# Hi_Current.net
KiCad netlist of a schematic drawn in Altium Designer
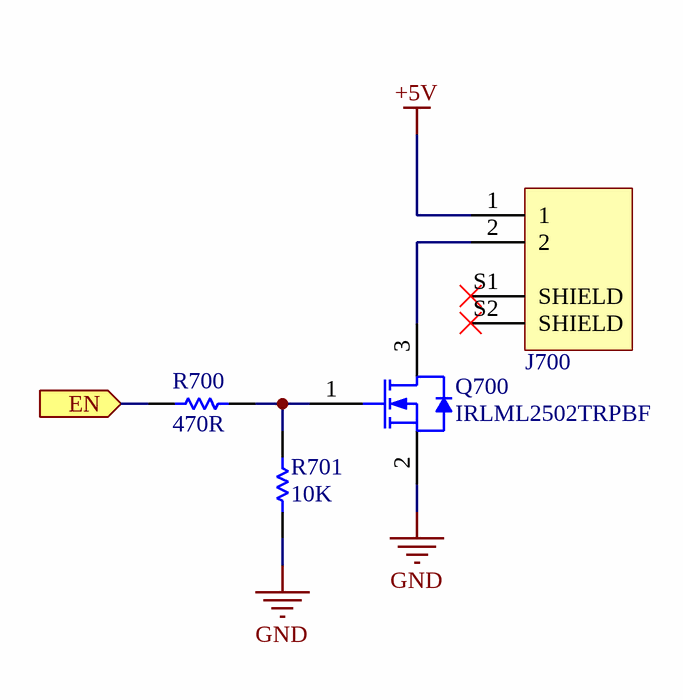
[diagram p0: Hi_Current.SchDoc]

(export (version "E")
  (design (tool "Eeschema 10.0.6"))
  (components
    (comp (ref "J700")
      (value "2 pin vertical JST GH")
      (footprint "JST_BM02B-GHS-TBT(LF)(SN)(N)")
      (description "JST GH vertical 2 pin\r\nDigiKey part no. 455-1578-1-ND")
      (fields (field (name "MF") "JST Sales") (field (name "DIGI-KEY_PART_NUMBER") "455-1580-1-ND"))
      (libsource (lib "Moonlight_Components") (part "BM02B-GHS-TBT(LF)(SN)(N)"))
    )
    (comp (ref "Q700")
      (value "IRLML2502TRPBF")
      (footprint "INTR-SOT-23-3_V")
      (description "N-Channel HEXFET(R) Power MOSFET, 20 V VDS, +/- 12 V VGS, 4.2 A, 3-Pin SOT23, RoHS, Tape and Reel")
      (fields (field (name "MANUFACTURER") "International Rectifier"))
      (libsource (lib "Moonlight_Components") (part "IRLML2502TRPBF"))
    )
    (comp (ref "R700")
      (value "470R")
      (footprint "0603_RES")
      (libsource (lib "Moonlight-Components") (part "Resistor"))
    )
    (comp (ref "R701")
      (value "10K")
      (footprint "0603_RES")
      (libsource (lib "Moonlight-Components") (part "Resistor"))
    )
  )
  (nets
    (net (code "1") (name "+5V") (class "Default")
      (node (ref "J700") (pin "1") (pinfunction "1_1") (pintype "passive"))
    )
    (net (code "2") (name "/EN") (class "Default")
      (node (ref "R700") (pin "1") (pinfunction "1_1") (pintype "passive"))
    )
    (net (code "3") (name "GND") (class "Default")
      (node (ref "Q700") (pin "2") (pinfunction "S_2") (pintype "passive"))
      (node (ref "R701") (pin "2") (pinfunction "2_2") (pintype "passive"))
    )
    (net (code "4") (name "Net-(Q700-D)") (class "Default")
      (node (ref "J700") (pin "2") (pinfunction "2_2") (pintype "passive"))
      (node (ref "Q700") (pin "3") (pinfunction "D_3") (pintype "passive"))
    )
    (net (code "5") (name "Net-(Q700-G)") (class "Default")
      (node (ref "Q700") (pin "1") (pinfunction "G_1") (pintype "passive"))
      (node (ref "R700") (pin "2") (pinfunction "2_2") (pintype "passive"))
      (node (ref "R701") (pin "1") (pinfunction "1_1") (pintype "passive"))
    )
    (net (code "6") (name "unconnected-(J700-SHIELD-PadS1)") (class "Default")
      (node (ref "J700") (pin "S1") (pinfunction "SHIELD_S1") (pintype "passive+no_connect"))
    )
    (net (code "7") (name "unconnected-(J700-SHIELD-PadS2)") (class "Default")
      (node (ref "J700") (pin "S2") (pinfunction "SHIELD_S2") (pintype "passive+no_connect"))
    )
  )
)
